# Linear_VCA_chip.net
KiCad netlist of a schematic drawn in EAGLE
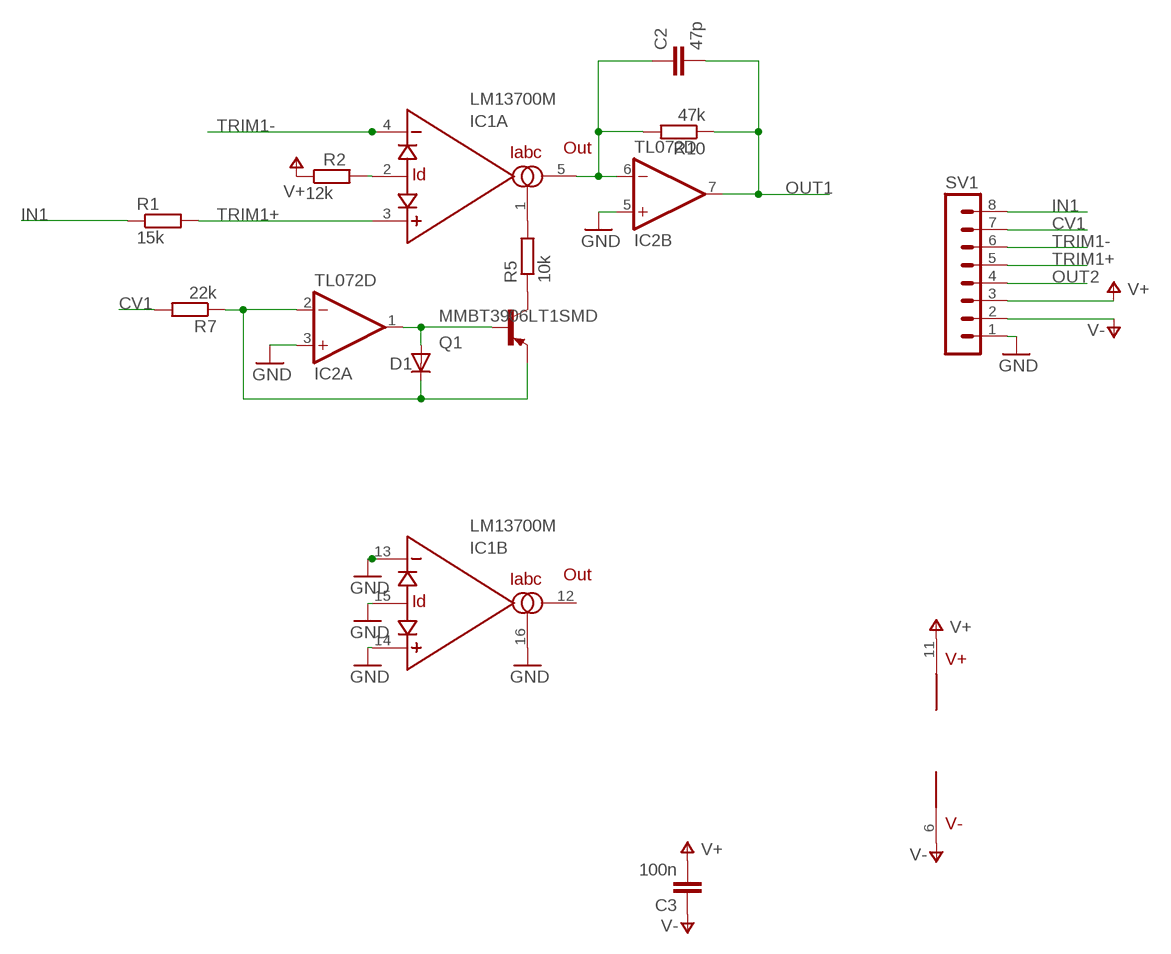
[diagram p0: schematic, sheet 1]

(export (version "E")
  (design (tool "Eeschema 10.0.6"))
  (components
    (comp (ref "C2")
      (value "47p")
      (footprint "eagle-import:C0805")
      (libsource (lib "eagle-import") (part "C-EUC0805"))
    )
    (comp (ref "C3")
      (value "100n")
      (footprint "eagle-import:C0805")
      (libsource (lib "eagle-import") (part "C-EUC0805"))
    )
    (comp (ref "D1")
      (value "DIODE-SOD80C")
      (footprint "eagle-import:SOD80C")
      (libsource (lib "eagle-import") (part "DIODE-SOD80C"))
    )
    (comp (ref "IC1")
      (value "LM13700M")
      (footprint "eagle-import:SO16")
      (libsource (lib "eagle-import") (part "LM13700M"))
    )
    (comp (ref "IC2")
      (value "TL072D")
      (footprint "eagle-import:SO08")
      (libsource (lib "eagle-import") (part "TL072D"))
    )
    (comp (ref "Q1")
      (value "MMBT3906LT1SMD")
      (footprint "eagle-import:SOT23-BEC")
      (libsource (lib "eagle-import") (part "MMBT3906SMDLT1"))
    )
    (comp (ref "R1")
      (value "15k")
      (footprint "eagle-import:R0805")
      (libsource (lib "eagle-import") (part "R-EU_R0805"))
    )
    (comp (ref "R2")
      (value "12k")
      (footprint "eagle-import:R0805")
      (libsource (lib "eagle-import") (part "R-EU_R0805"))
    )
    (comp (ref "R5")
      (value "10k")
      (footprint "eagle-import:R0805")
      (libsource (lib "eagle-import") (part "R-EU_R0805"))
    )
    (comp (ref "R7")
      (value "22k")
      (footprint "eagle-import:R0805")
      (libsource (lib "eagle-import") (part "R-EU_R0805"))
    )
    (comp (ref "R10")
      (value "47k")
      (footprint "eagle-import:R0805")
      (libsource (lib "eagle-import") (part "R-EU_R0805"))
    )
    (comp (ref "SV1")
      (value "MA08-1")
      (footprint "eagle-import:MA08-1")
      (libsource (lib "eagle-import") (part "MA08-1"))
    )
  )
  (nets
    (net (code "1") (name "/CV1") (class "Default")
      (node (ref "R7") (pin "2") (pinfunction "2_2") (pintype "passive"))
      (node (ref "SV1") (pin "7") (pinfunction "7_7") (pintype "passive"))
    )
    (net (code "2") (name "/IN1") (class "Default")
      (node (ref "R1") (pin "1") (pinfunction "1_1") (pintype "passive"))
      (node (ref "SV1") (pin "8") (pinfunction "8_8") (pintype "passive"))
    )
    (net (code "3") (name "/OUT1") (class "Default")
      (node (ref "C2") (pin "2") (pinfunction "2_2") (pintype "passive"))
      (node (ref "IC2") (pin "7") (pinfunction "OUT_7") (pintype "output"))
      (node (ref "R10") (pin "1") (pinfunction "1_1") (pintype "passive"))
    )
    (net (code "4") (name "/OUT2") (class "Default")
      (node (ref "SV1") (pin "4") (pinfunction "4_4") (pintype "passive"))
    )
    (net (code "5") (name "/TRIM1+") (class "Default")
      (node (ref "IC1") (pin "3") (pinfunction "+IN_3") (pintype "bidirectional"))
      (node (ref "R1") (pin "2") (pinfunction "2_2") (pintype "passive"))
      (node (ref "SV1") (pin "5") (pinfunction "5_5") (pintype "passive"))
    )
    (net (code "6") (name "/TRIM1-") (class "Default")
      (node (ref "IC1") (pin "4") (pinfunction "-IN_4") (pintype "bidirectional"))
      (node (ref "SV1") (pin "6") (pinfunction "6_6") (pintype "passive"))
    )
    (net (code "7") (name "GND") (class "Default")
      (node (ref "IC1") (pin "13") (pinfunction "-IN_13") (pintype "bidirectional"))
      (node (ref "IC1") (pin "14") (pinfunction "+IN_14") (pintype "bidirectional"))
      (node (ref "IC1") (pin "15") (pinfunction "ID_15") (pintype "bidirectional"))
      (node (ref "IC1") (pin "16") (pinfunction "IABC_16") (pintype "bidirectional"))
      (node (ref "IC2") (pin "3") (pinfunction "+IN_3") (pintype "input"))
      (node (ref "IC2") (pin "5") (pinfunction "+IN_5") (pintype "input"))
      (node (ref "SV1") (pin "1") (pinfunction "1_1") (pintype "passive"))
    )
    (net (code "8") (name "Net-(IC1A-IABC)") (class "Default")
      (node (ref "IC1") (pin "1") (pinfunction "IABC_1") (pintype "bidirectional"))
      (node (ref "R5") (pin "2") (pinfunction "2_2") (pintype "passive"))
    )
    (net (code "9") (name "Net-(IC1A-ID)") (class "Default")
      (node (ref "IC1") (pin "2") (pinfunction "ID_2") (pintype "bidirectional"))
      (node (ref "R2") (pin "2") (pinfunction "2_2") (pintype "passive"))
    )
    (net (code "10") (name "Net-(IC1A-OUT)") (class "Default")
      (node (ref "C2") (pin "1") (pinfunction "1_1") (pintype "passive"))
      (node (ref "IC1") (pin "5") (pinfunction "OUT_5") (pintype "bidirectional"))
      (node (ref "IC2") (pin "6") (pinfunction "-IN_6") (pintype "input"))
      (node (ref "R10") (pin "2") (pinfunction "2_2") (pintype "passive"))
    )
    (net (code "11") (name "Net-(IC2A--IN)") (class "Default")
      (node (ref "D1") (pin "C") (pinfunction "C_C") (pintype "passive"))
      (node (ref "IC2") (pin "2") (pinfunction "-IN_2") (pintype "input"))
      (node (ref "Q1") (pin "E") (pinfunction "E_E") (pintype "passive"))
      (node (ref "R7") (pin "1") (pinfunction "1_1") (pintype "passive"))
    )
    (net (code "12") (name "Net-(IC2A-OUT)") (class "Default")
      (node (ref "D1") (pin "A") (pinfunction "A_A") (pintype "passive"))
      (node (ref "IC2") (pin "1") (pinfunction "OUT_1") (pintype "output"))
      (node (ref "Q1") (pin "B") (pinfunction "B_B") (pintype "passive"))
    )
    (net (code "13") (name "Net-(Q1-PadC)") (class "Default")
      (node (ref "Q1") (pin "C") (pinfunction "C_C") (pintype "passive"))
      (node (ref "R5") (pin "1") (pinfunction "1_1") (pintype "passive"))
    )
    (net (code "14") (name "V+") (class "Default")
      (node (ref "C3") (pin "2") (pinfunction "2_2") (pintype "passive"))
      (node (ref "IC1") (pin "11") (pinfunction "V+_11") (pintype "bidirectional"))
      (node (ref "R2") (pin "1") (pinfunction "1_1") (pintype "passive"))
      (node (ref "SV1") (pin "3") (pinfunction "3_3") (pintype "passive"))
    )
    (net (code "15") (name "V-") (class "Default")
      (node (ref "C3") (pin "1") (pinfunction "1_1") (pintype "passive"))
      (node (ref "IC1") (pin "6") (pinfunction "V-_6") (pintype "bidirectional"))
      (node (ref "SV1") (pin "2") (pinfunction "2_2") (pintype "passive"))
    )
    (net (code "16") (name "unconnected-(IC1B-OUT-Pad12)") (class "Default")
      (node (ref "IC1") (pin "12") (pinfunction "OUT_12") (pintype "bidirectional"))
    )
  )
)
